# room_interface.net
KiCad netlist of a schematic drawn in EAGLE
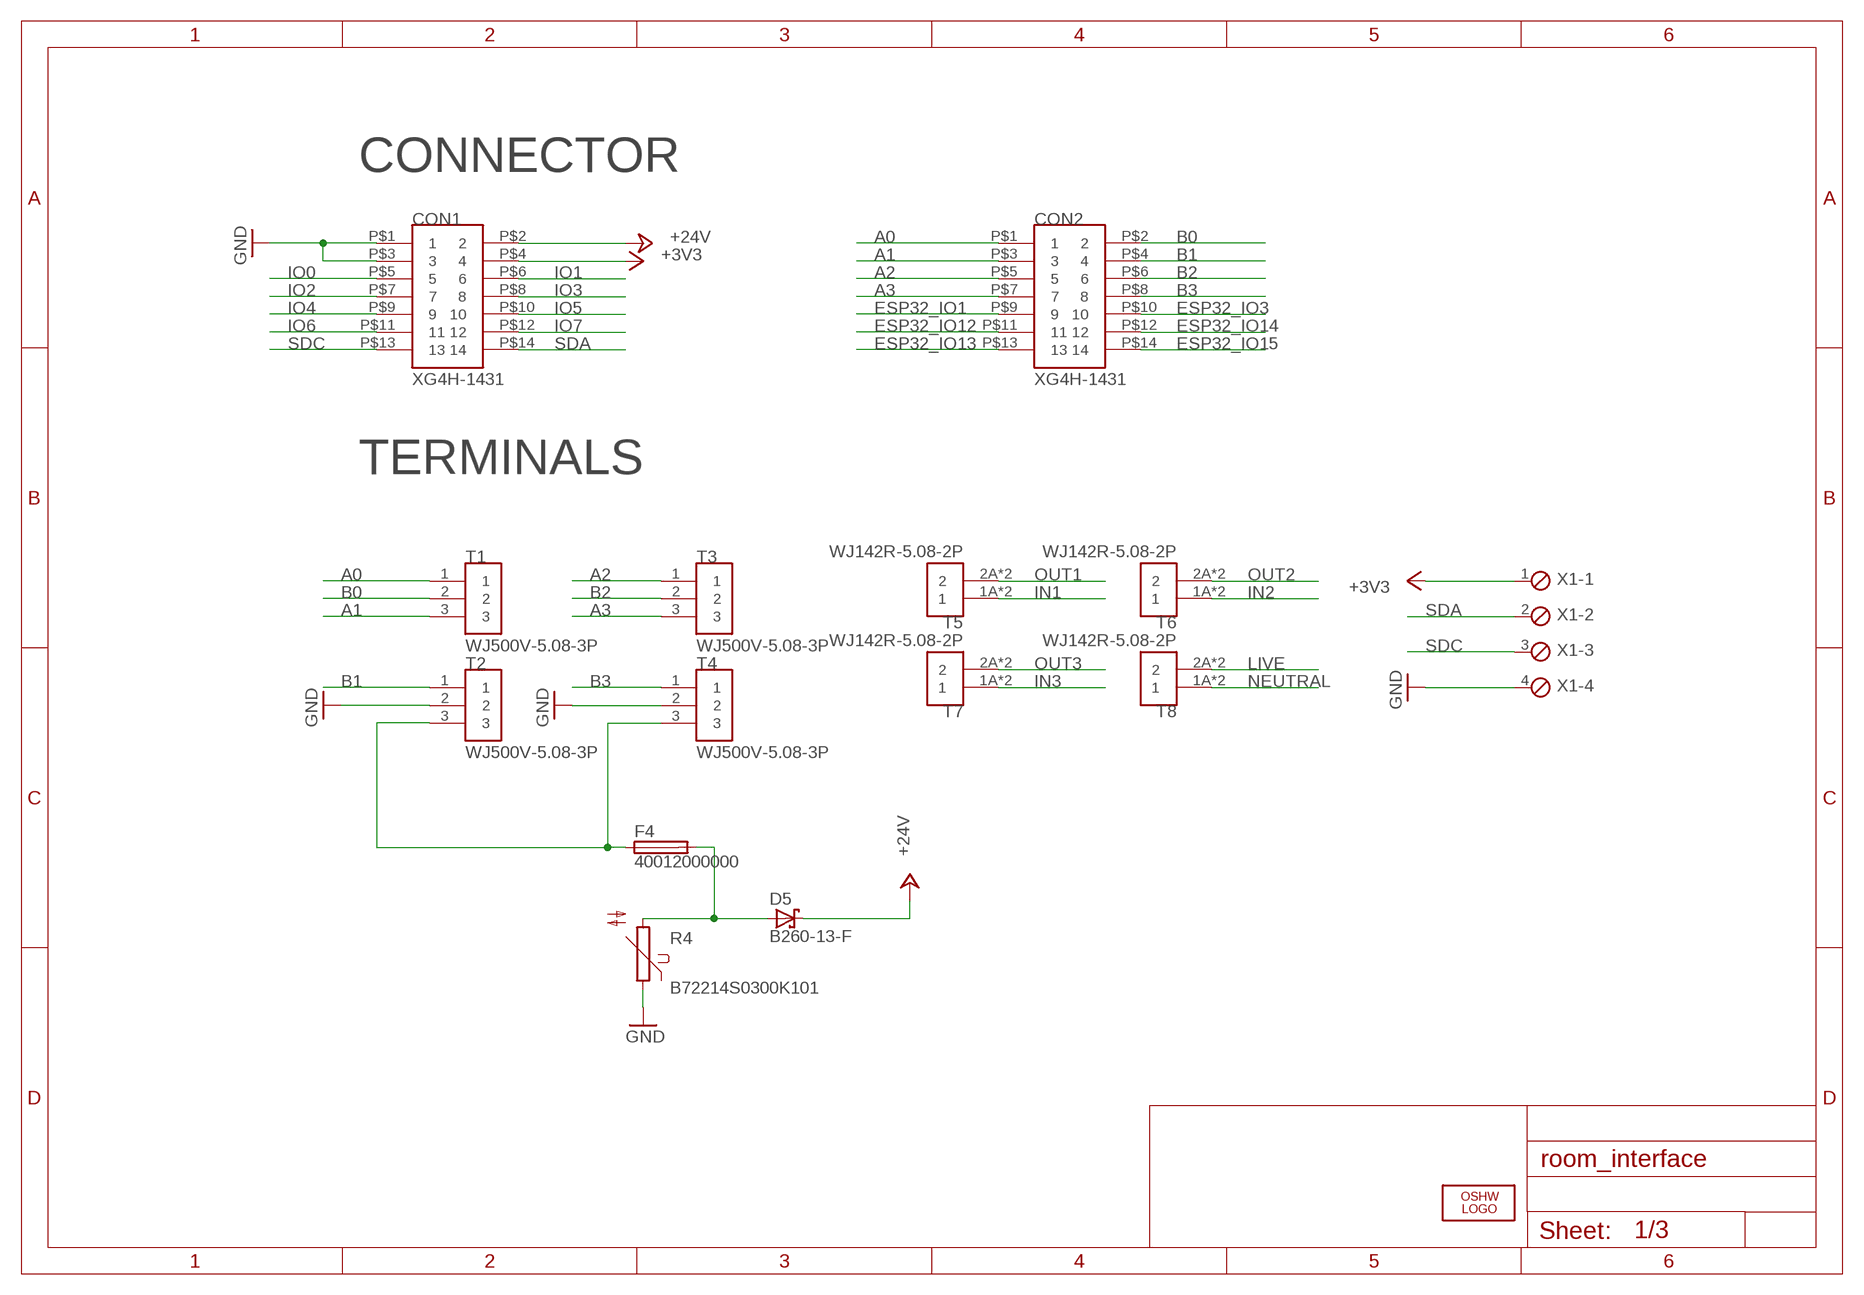
[diagram p0: schematic, sheet 1]
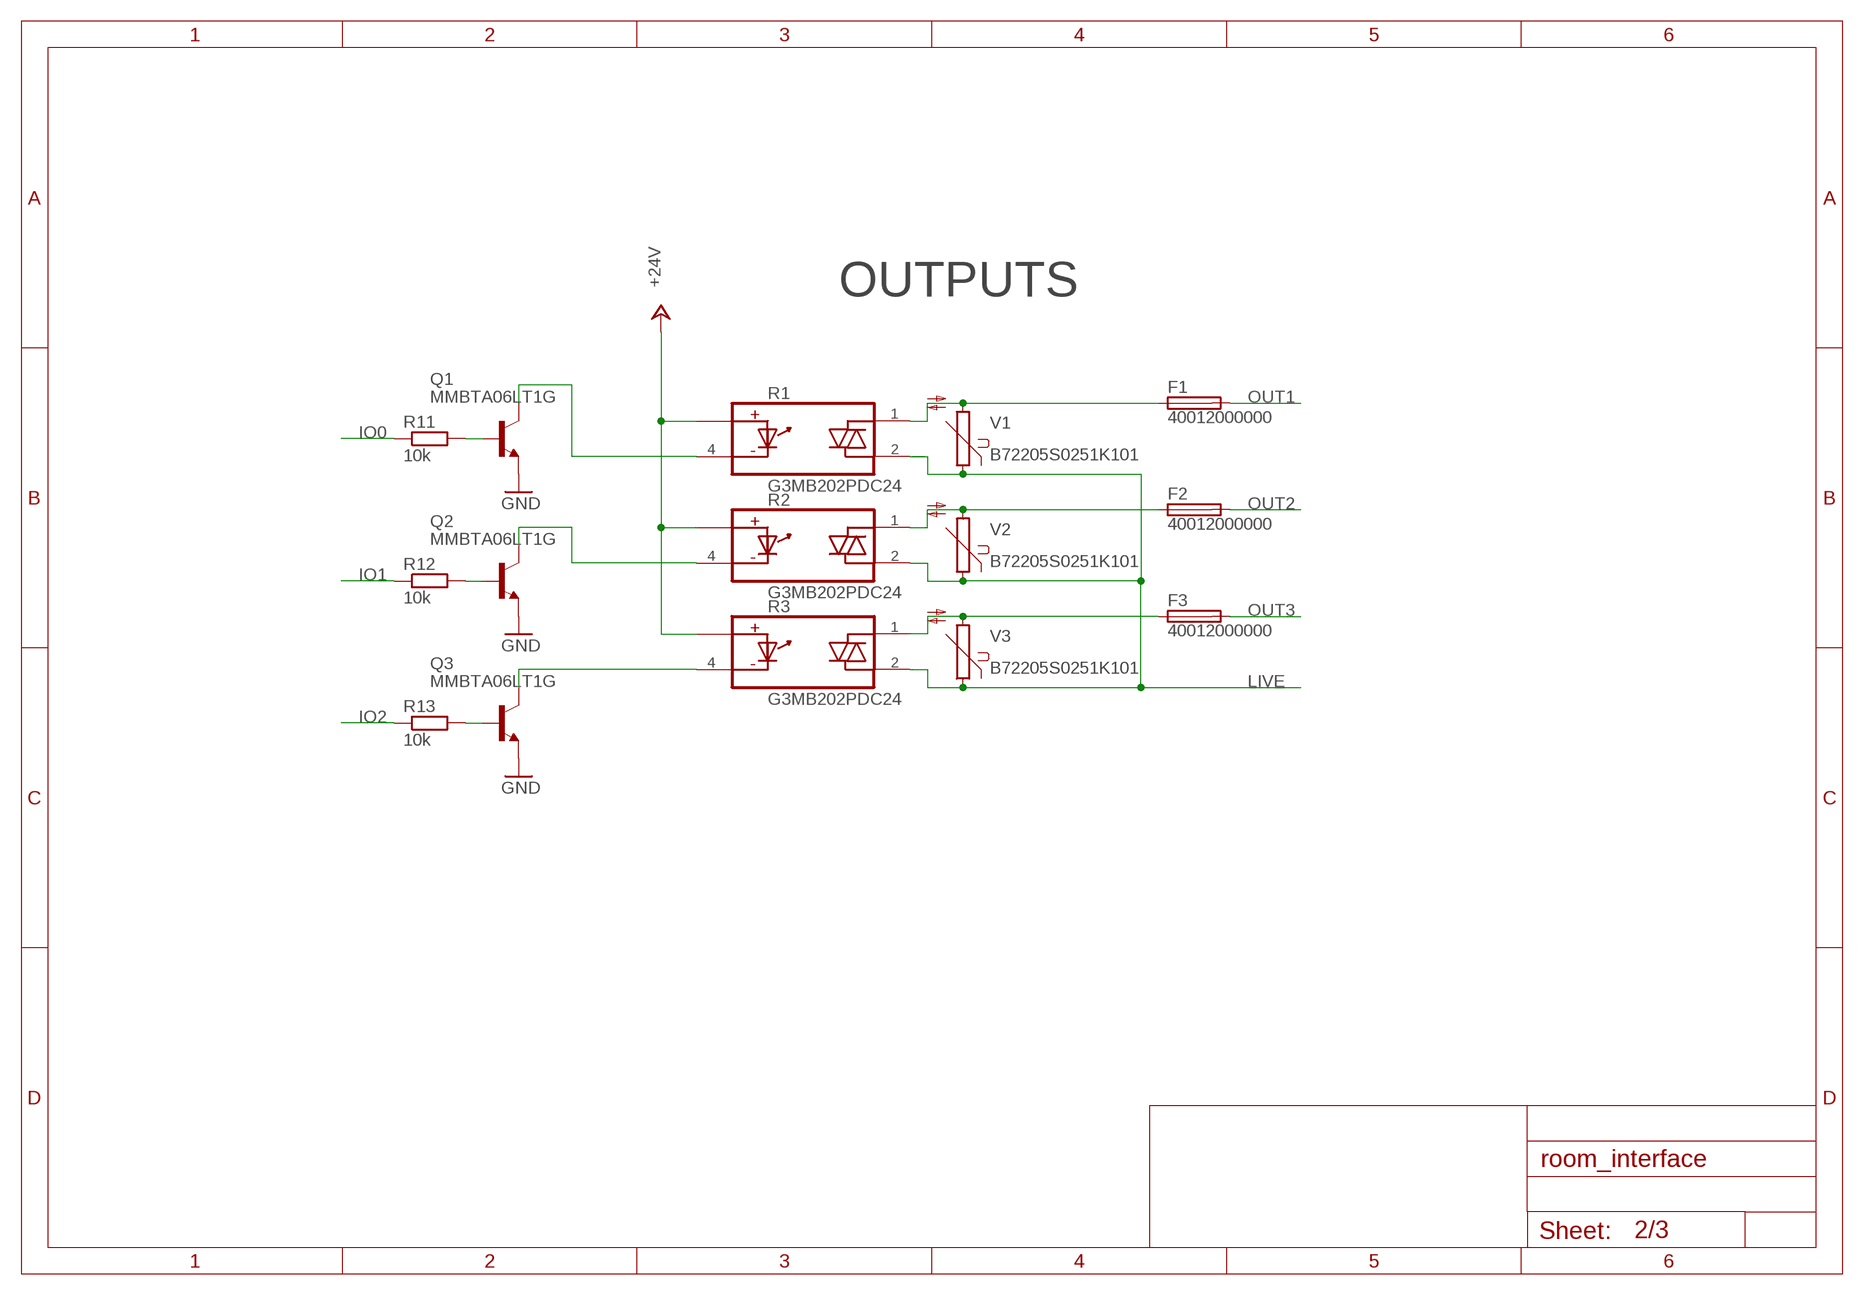
[diagram p1: schematic, sheet 2]
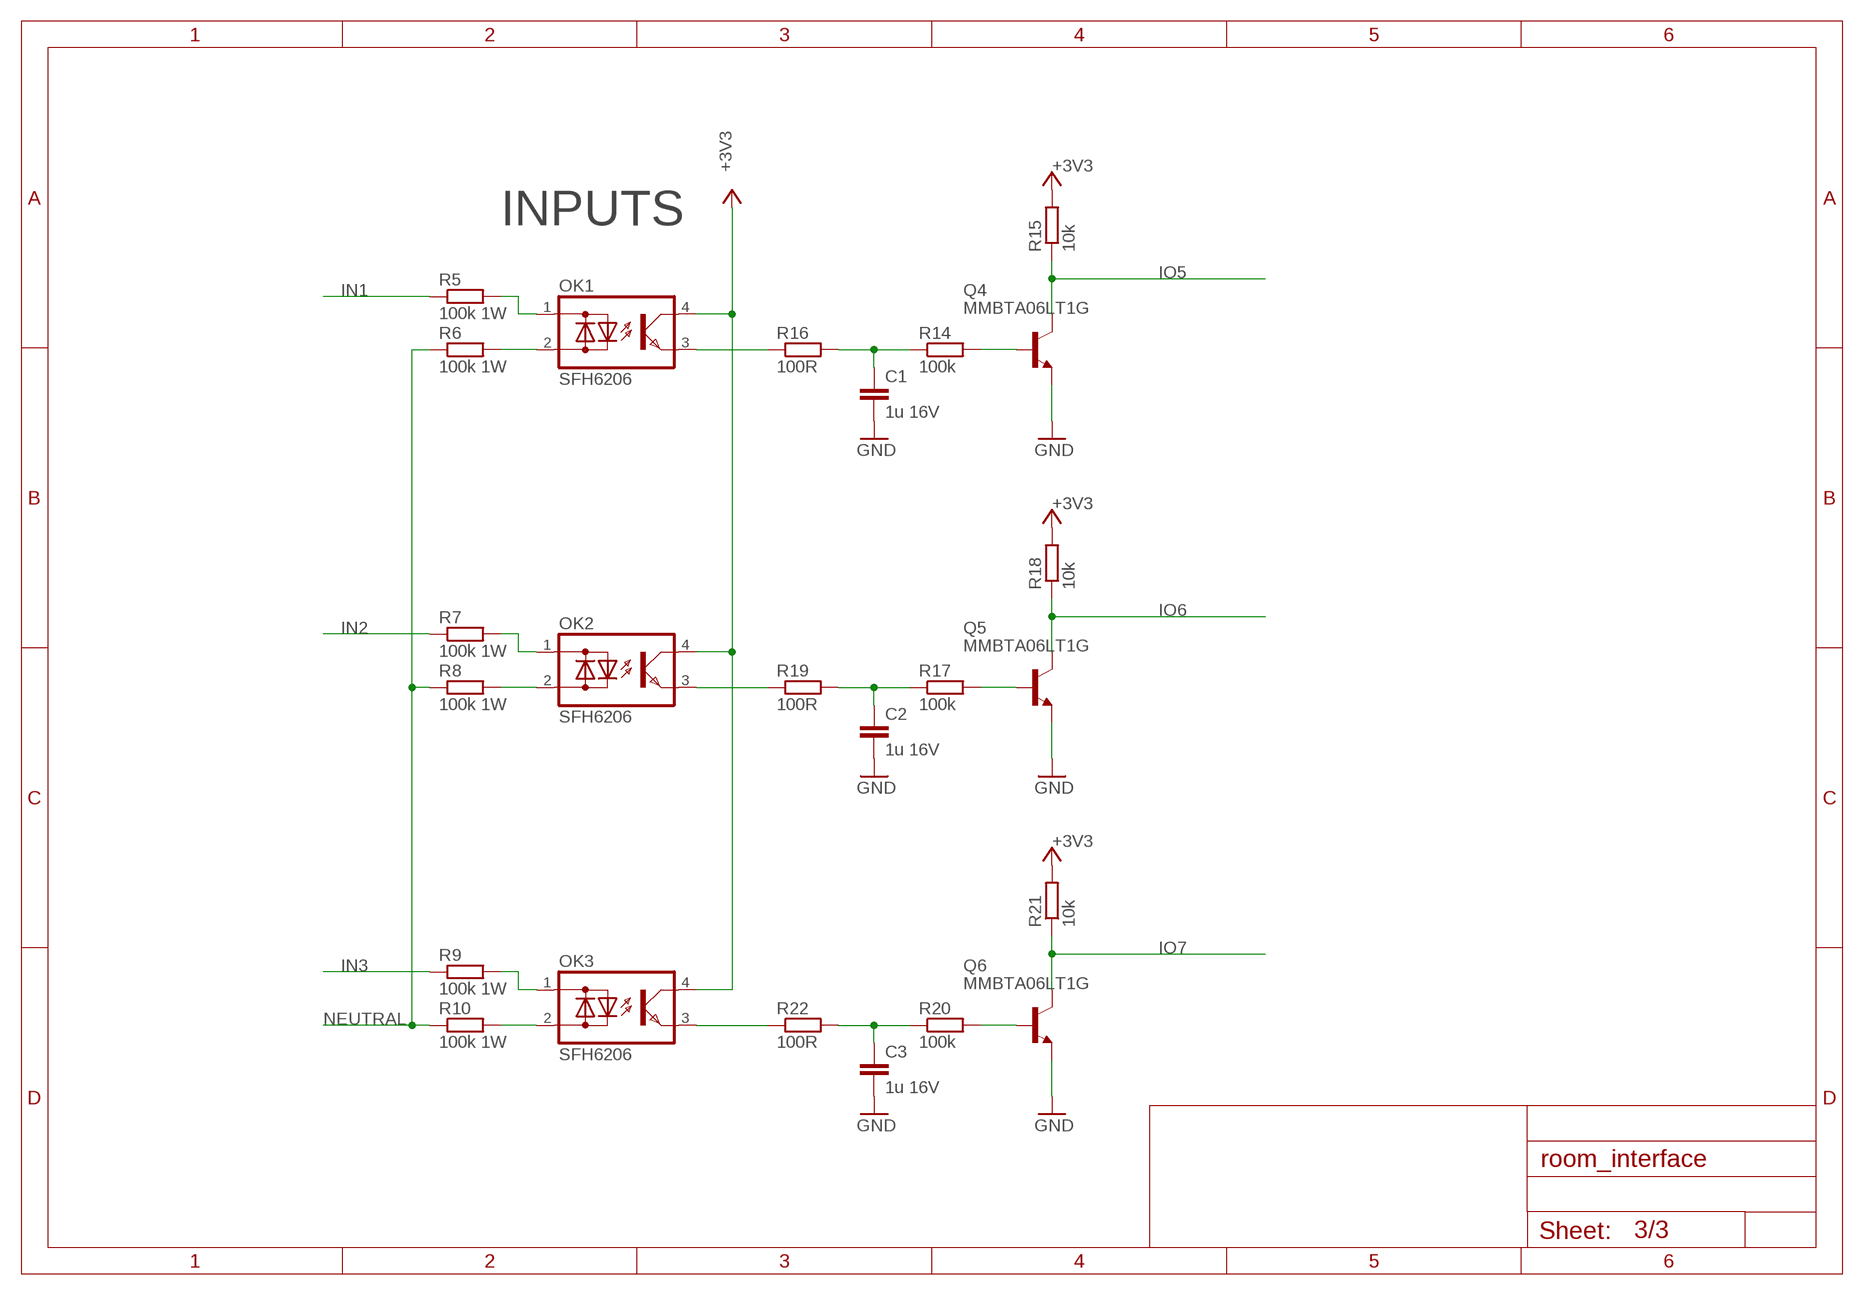
[diagram p2: schematic, sheet 3]

(export (version "E")
  (design (tool "Eeschema 10.0.6"))
  (components
    (comp (ref "C1")
      (value "1u 16V")
      (footprint "eagle-import:C0805")
      (libsource (lib "eagle-import") (part "C-EUC0805"))
    )
    (comp (ref "C2")
      (value "1u 16V")
      (footprint "eagle-import:C0805")
      (libsource (lib "eagle-import") (part "C-EUC0805"))
    )
    (comp (ref "C3")
      (value "1u 16V")
      (footprint "eagle-import:C0805")
      (libsource (lib "eagle-import") (part "C-EUC0805"))
    )
    (comp (ref "OK1")
      (value "SFH6206")
      (footprint "eagle-import:DIL4-SMD")
      (fields (field (name "MF") "VISHAY/TELEFUNKEN") (field (name "MPN") "SFH6206-3"))
      (libsource (lib "eagle-import") (part "SFH6206"))
    )
    (comp (ref "OK2")
      (value "SFH6206")
      (footprint "eagle-import:DIL4-SMD")
      (fields (field (name "MF") "VISHAY/TELEFUNKEN") (field (name "MPN") "SFH6206-3"))
      (libsource (lib "eagle-import") (part "SFH6206"))
    )
    (comp (ref "OK3")
      (value "SFH6206")
      (footprint "eagle-import:DIL4-SMD")
      (fields (field (name "MF") "VISHAY/TELEFUNKEN") (field (name "MPN") "SFH6206-3"))
      (libsource (lib "eagle-import") (part "SFH6206"))
    )
    (comp (ref "Q4")
      (value "MMBTA06LT1G")
      (footprint "eagle-import:SOT23-BEC")
      (libsource (lib "eagle-import") (part "BC849SMD"))
    )
    (comp (ref "Q5")
      (value "MMBTA06LT1G")
      (footprint "eagle-import:SOT23-BEC")
      (libsource (lib "eagle-import") (part "BC849SMD"))
    )
    (comp (ref "Q6")
      (value "MMBTA06LT1G")
      (footprint "eagle-import:SOT23-BEC")
      (libsource (lib "eagle-import") (part "BC849SMD"))
    )
    (comp (ref "R5")
      (value "100k 1W")
      (footprint "eagle-import:R2010")
      (libsource (lib "eagle-import") (part "R-EU_R2010"))
    )
    (comp (ref "R6")
      (value "100k 1W")
      (footprint "eagle-import:R2010")
      (libsource (lib "eagle-import") (part "R-EU_R2010"))
    )
    (comp (ref "R7")
      (value "100k 1W")
      (footprint "eagle-import:R2010")
      (libsource (lib "eagle-import") (part "R-EU_R2010"))
    )
    (comp (ref "R8")
      (value "100k 1W")
      (footprint "eagle-import:R2010")
      (libsource (lib "eagle-import") (part "R-EU_R2010"))
    )
    (comp (ref "R9")
      (value "100k 1W")
      (footprint "eagle-import:R2010")
      (libsource (lib "eagle-import") (part "R-EU_R2010"))
    )
    (comp (ref "R10")
      (value "100k 1W")
      (footprint "eagle-import:R2010")
      (libsource (lib "eagle-import") (part "R-EU_R2010"))
    )
    (comp (ref "R14")
      (value "100k")
      (footprint "eagle-import:R1206")
      (libsource (lib "eagle-import") (part "R-EU_R1206"))
    )
    (comp (ref "R15")
      (value "10k")
      (footprint "eagle-import:R1206")
      (libsource (lib "eagle-import") (part "R-EU_R1206"))
    )
    (comp (ref "R16")
      (value "100R")
      (footprint "eagle-import:R1206")
      (libsource (lib "eagle-import") (part "R-EU_R1206"))
    )
    (comp (ref "R17")
      (value "100k")
      (footprint "eagle-import:R1206")
      (libsource (lib "eagle-import") (part "R-EU_R1206"))
    )
    (comp (ref "R18")
      (value "10k")
      (footprint "eagle-import:R1206")
      (libsource (lib "eagle-import") (part "R-EU_R1206"))
    )
    (comp (ref "R19")
      (value "100R")
      (footprint "eagle-import:R1206")
      (libsource (lib "eagle-import") (part "R-EU_R1206"))
    )
    (comp (ref "R20")
      (value "100k")
      (footprint "eagle-import:R1206")
      (libsource (lib "eagle-import") (part "R-EU_R1206"))
    )
    (comp (ref "R21")
      (value "10k")
      (footprint "eagle-import:R1206")
      (libsource (lib "eagle-import") (part "R-EU_R1206"))
    )
    (comp (ref "R22")
      (value "100R")
      (footprint "eagle-import:R1206")
      (libsource (lib "eagle-import") (part "R-EU_R1206"))
    )
    (comp (ref "CON1")
      (value "XG4H-1431")
      (footprint "eagle-import:XG4H-1431")
      (libsource (lib "eagle-import") (part "XG4H-1431"))
    )
    (comp (ref "CON2")
      (value "XG4H-1431")
      (footprint "eagle-import:XG4H-1431")
      (libsource (lib "eagle-import") (part "XG4H-1431"))
    )
    (comp (ref "D5")
      (value "B260-13-F")
      (footprint "eagle-import:SMB")
      (libsource (lib "eagle-import") (part "MBRS130LT3"))
    )
    (comp (ref "F4")
      (value "40012000000")
      (footprint "eagle-import:400")
      (libsource (lib "eagle-import") (part "40012000000"))
    )
    (comp (ref "LOGO1")
      (value "OSHW_LOGO_FILLX0350-NT")
      (footprint "eagle-import:OSHW_FILLX350_NOTEXT")
      (libsource (lib "eagle-import") (part "OSHW_LOGO_FILLX0350-NT"))
    )
    (comp (ref "R4")
      (value "B72214S0300K101")
      (footprint "eagle-import:S14K300")
      (libsource (lib "eagle-import") (part "S14K300"))
    )
    (comp (ref "T1")
      (value "WJ500V-5.08-3P")
      (footprint "eagle-import:WJ500V-5.08-3P")
      (libsource (lib "eagle-import") (part "WJ500V-5.08-3P"))
    )
    (comp (ref "T2")
      (value "WJ500V-5.08-3P")
      (footprint "eagle-import:WJ500V-5.08-3P")
      (libsource (lib "eagle-import") (part "WJ500V-5.08-3P"))
    )
    (comp (ref "T3")
      (value "WJ500V-5.08-3P")
      (footprint "eagle-import:WJ500V-5.08-3P")
      (libsource (lib "eagle-import") (part "WJ500V-5.08-3P"))
    )
    (comp (ref "T4")
      (value "WJ500V-5.08-3P")
      (footprint "eagle-import:WJ500V-5.08-3P")
      (libsource (lib "eagle-import") (part "WJ500V-5.08-3P"))
    )
    (comp (ref "T5")
      (value "WJ142R-5.08-2P")
      (footprint "eagle-import:WJ142R.5.08-2P")
      (libsource (lib "eagle-import") (part "WJ142R-5.08-2P"))
    )
    (comp (ref "T6")
      (value "WJ142R-5.08-2P")
      (footprint "eagle-import:WJ142R.5.08-2P")
      (libsource (lib "eagle-import") (part "WJ142R-5.08-2P"))
    )
    (comp (ref "T7")
      (value "WJ142R-5.08-2P")
      (footprint "eagle-import:WJ142R.5.08-2P")
      (libsource (lib "eagle-import") (part "WJ142R-5.08-2P"))
    )
    (comp (ref "T8")
      (value "WJ142R-5.08-2P")
      (footprint "eagle-import:WJ142R.5.08-2P")
      (libsource (lib "eagle-import") (part "WJ142R-5.08-2P"))
    )
    (comp (ref "X1")
      (value "MPT4")
      (footprint "eagle-import:4POL254")
      (libsource (lib "eagle-import") (part "MPT4"))
    )
    (comp (ref "F1")
      (value "40012000000")
      (footprint "eagle-import:400")
      (libsource (lib "eagle-import") (part "40012000000"))
    )
    (comp (ref "F2")
      (value "40012000000")
      (footprint "eagle-import:400")
      (libsource (lib "eagle-import") (part "40012000000"))
    )
    (comp (ref "F3")
      (value "40012000000")
      (footprint "eagle-import:400")
      (libsource (lib "eagle-import") (part "40012000000"))
    )
    (comp (ref "Q1")
      (value "MMBTA06LT1G")
      (footprint "eagle-import:SOT23-BEC")
      (libsource (lib "eagle-import") (part "BC849SMD"))
    )
    (comp (ref "Q2")
      (value "MMBTA06LT1G")
      (footprint "eagle-import:SOT23-BEC")
      (libsource (lib "eagle-import") (part "BC849SMD"))
    )
    (comp (ref "Q3")
      (value "MMBTA06LT1G")
      (footprint "eagle-import:SOT23-BEC")
      (libsource (lib "eagle-import") (part "BC849SMD"))
    )
    (comp (ref "R1")
      (value "G3MB202PDC24")
      (footprint "eagle-import:RELAY_G3MB202PDC12")
      (libsource (lib "eagle-import") (part "RELAY_G3MB202PDC5"))
    )
    (comp (ref "R2")
      (value "G3MB202PDC24")
      (footprint "eagle-import:RELAY_G3MB202PDC12")
      (libsource (lib "eagle-import") (part "RELAY_G3MB202PDC5"))
    )
    (comp (ref "R3")
      (value "G3MB202PDC24")
      (footprint "eagle-import:RELAY_G3MB202PDC12")
      (libsource (lib "eagle-import") (part "RELAY_G3MB202PDC5"))
    )
    (comp (ref "R11")
      (value "10k")
      (footprint "eagle-import:R1206")
      (libsource (lib "eagle-import") (part "R-EU_R1206"))
    )
    (comp (ref "R12")
      (value "10k")
      (footprint "eagle-import:R1206")
      (libsource (lib "eagle-import") (part "R-EU_R1206"))
    )
    (comp (ref "R13")
      (value "10k")
      (footprint "eagle-import:R1206")
      (libsource (lib "eagle-import") (part "R-EU_R1206"))
    )
    (comp (ref "V1")
      (value "B72205S0251K101")
      (footprint "eagle-import:S05K250")
      (libsource (lib "eagle-import") (part "S05K250"))
    )
    (comp (ref "V2")
      (value "B72205S0251K101")
      (footprint "eagle-import:S05K250")
      (libsource (lib "eagle-import") (part "S05K250"))
    )
    (comp (ref "V3")
      (value "B72205S0251K101")
      (footprint "eagle-import:S05K250")
      (libsource (lib "eagle-import") (part "S05K250"))
    )
  )
  (nets
    (net (code "1") (name "+3V3") (class "Default")
      (node (ref "CON1") (pin "P$4") (pinfunction "4_P$4") (pintype "passive"))
      (node (ref "OK1") (pin "4") (pinfunction "C_4") (pintype "passive"))
      (node (ref "OK2") (pin "4") (pinfunction "C_4") (pintype "passive"))
      (node (ref "OK3") (pin "4") (pinfunction "C_4") (pintype "passive"))
      (node (ref "R15") (pin "2") (pinfunction "2_2") (pintype "passive"))
      (node (ref "R18") (pin "2") (pinfunction "2_2") (pintype "passive"))
      (node (ref "R21") (pin "2") (pinfunction "2_2") (pintype "passive"))
      (node (ref "X1") (pin "1") (pinfunction "1_1") (pintype "passive"))
    )
    (net (code "2") (name "+24V") (class "Default")
      (node (ref "CON1") (pin "P$2") (pinfunction "2_P$2") (pintype "passive"))
      (node (ref "D5") (pin "C") (pinfunction "C_C") (pintype "passive"))
      (node (ref "R1") (pin "3") (pinfunction "IN+_3") (pintype "input"))
      (node (ref "R2") (pin "3") (pinfunction "IN+_3") (pintype "input"))
      (node (ref "R3") (pin "3") (pinfunction "IN+_3") (pintype "input"))
    )
    (net (code "3") (name "A0") (class "Default")
      (node (ref "CON2") (pin "P$1") (pinfunction "1_P$1") (pintype "passive"))
      (node (ref "T1") (pin "1") (pinfunction "1_1") (pintype "passive"))
    )
    (net (code "4") (name "A1") (class "Default")
      (node (ref "CON2") (pin "P$3") (pinfunction "3_P$3") (pintype "passive"))
      (node (ref "T1") (pin "3") (pinfunction "3_3") (pintype "passive"))
    )
    (net (code "5") (name "A2") (class "Default")
      (node (ref "CON2") (pin "P$5") (pinfunction "5_P$5") (pintype "passive"))
      (node (ref "T3") (pin "1") (pinfunction "1_1") (pintype "passive"))
    )
    (net (code "6") (name "A3") (class "Default")
      (node (ref "CON2") (pin "P$7") (pinfunction "7_P$7") (pintype "passive"))
      (node (ref "T3") (pin "3") (pinfunction "3_3") (pintype "passive"))
    )
    (net (code "7") (name "B0") (class "Default")
      (node (ref "CON2") (pin "P$2") (pinfunction "2_P$2") (pintype "passive"))
      (node (ref "T1") (pin "2") (pinfunction "2_2") (pintype "passive"))
    )
    (net (code "8") (name "B1") (class "Default")
      (node (ref "CON2") (pin "P$4") (pinfunction "4_P$4") (pintype "passive"))
      (node (ref "T2") (pin "1") (pinfunction "1_1") (pintype "passive"))
    )
    (net (code "9") (name "B2") (class "Default")
      (node (ref "CON2") (pin "P$6") (pinfunction "6_P$6") (pintype "passive"))
      (node (ref "T3") (pin "2") (pinfunction "2_2") (pintype "passive"))
    )
    (net (code "10") (name "B3") (class "Default")
      (node (ref "CON2") (pin "P$8") (pinfunction "8_P$8") (pintype "passive"))
      (node (ref "T4") (pin "1") (pinfunction "1_1") (pintype "passive"))
    )
    (net (code "11") (name "ESP32_IO1") (class "Default")
      (node (ref "CON2") (pin "P$9") (pinfunction "9_P$9") (pintype "passive"))
    )
    (net (code "12") (name "ESP32_IO3") (class "Default")
      (node (ref "CON2") (pin "P$10") (pinfunction "10_P$10") (pintype "passive"))
    )
    (net (code "13") (name "ESP32_IO12") (class "Default")
      (node (ref "CON2") (pin "P$11") (pinfunction "11_P$11") (pintype "passive"))
    )
    (net (code "14") (name "ESP32_IO13") (class "Default")
      (node (ref "CON2") (pin "P$13") (pinfunction "13_P$13") (pintype "passive"))
    )
    (net (code "15") (name "ESP32_IO14") (class "Default")
      (node (ref "CON2") (pin "P$12") (pinfunction "12_P$12") (pintype "passive"))
    )
    (net (code "16") (name "ESP32_IO15") (class "Default")
      (node (ref "CON2") (pin "P$14") (pinfunction "14_P$14") (pintype "passive"))
    )
    (net (code "17") (name "GND") (class "Default")
      (node (ref "C1") (pin "2") (pinfunction "2_2") (pintype "passive"))
      (node (ref "C2") (pin "2") (pinfunction "2_2") (pintype "passive"))
      (node (ref "C3") (pin "2") (pinfunction "2_2") (pintype "passive"))
      (node (ref "CON1") (pin "P$1") (pinfunction "1_P$1") (pintype "passive"))
      (node (ref "CON1") (pin "P$3") (pinfunction "3_P$3") (pintype "passive"))
      (node (ref "Q1") (pin "E") (pinfunction "E_E") (pintype "passive"))
      (node (ref "Q2") (pin "E") (pinfunction "E_E") (pintype "passive"))
      (node (ref "Q3") (pin "E") (pinfunction "E_E") (pintype "passive"))
      (node (ref "Q4") (pin "E") (pinfunction "E_E") (pintype "passive"))
      (node (ref "Q5") (pin "E") (pinfunction "E_E") (pintype "passive"))
      (node (ref "Q6") (pin "E") (pinfunction "E_E") (pintype "passive"))
      (node (ref "R4") (pin "1") (pinfunction "1_1") (pintype "passive"))
      (node (ref "T2") (pin "2") (pinfunction "2_2") (pintype "passive"))
      (node (ref "T4") (pin "2") (pinfunction "2_2") (pintype "passive"))
      (node (ref "X1") (pin "4") (pinfunction "1_4") (pintype "passive"))
    )
    (net (code "18") (name "IN1") (class "Default")
      (node (ref "R5") (pin "1") (pinfunction "1_1") (pintype "passive"))
      (node (ref "T5") (pin "1A") (pinfunction "1_1A") (pintype "passive"))
      (node (ref "T5") (pin "1B") (pinfunction "1_1B") (pintype "passive"))
    )
    (net (code "19") (name "IN2") (class "Default")
      (node (ref "R7") (pin "1") (pinfunction "1_1") (pintype "passive"))
      (node (ref "T6") (pin "1A") (pinfunction "1_1A") (pintype "passive"))
      (node (ref "T6") (pin "1B") (pinfunction "1_1B") (pintype "passive"))
    )
    (net (code "20") (name "IN3") (class "Default")
      (node (ref "R9") (pin "1") (pinfunction "1_1") (pintype "passive"))
      (node (ref "T7") (pin "1A") (pinfunction "1_1A") (pintype "passive"))
      (node (ref "T7") (pin "1B") (pinfunction "1_1B") (pintype "passive"))
    )
    (net (code "21") (name "IO0") (class "Default")
      (node (ref "CON1") (pin "P$5") (pinfunction "5_P$5") (pintype "passive"))
      (node (ref "R11") (pin "1") (pinfunction "1_1") (pintype "passive"))
    )
    (net (code "22") (name "IO1") (class "Default")
      (node (ref "CON1") (pin "P$6") (pinfunction "6_P$6") (pintype "passive"))
      (node (ref "R12") (pin "1") (pinfunction "1_1") (pintype "passive"))
    )
    (net (code "23") (name "IO2") (class "Default")
      (node (ref "CON1") (pin "P$7") (pinfunction "7_P$7") (pintype "passive"))
      (node (ref "R13") (pin "1") (pinfunction "1_1") (pintype "passive"))
    )
    (net (code "24") (name "IO3") (class "Default")
      (node (ref "CON1") (pin "P$8") (pinfunction "8_P$8") (pintype "passive"))
    )
    (net (code "25") (name "IO4") (class "Default")
      (node (ref "CON1") (pin "P$9") (pinfunction "9_P$9") (pintype "passive"))
    )
    (net (code "26") (name "IO5") (class "Default")
      (node (ref "CON1") (pin "P$10") (pinfunction "10_P$10") (pintype "passive"))
      (node (ref "Q4") (pin "C") (pinfunction "C_C") (pintype "passive"))
      (node (ref "R15") (pin "1") (pinfunction "1_1") (pintype "passive"))
    )
    (net (code "27") (name "IO6") (class "Default")
      (node (ref "CON1") (pin "P$11") (pinfunction "11_P$11") (pintype "passive"))
      (node (ref "Q5") (pin "C") (pinfunction "C_C") (pintype "passive"))
      (node (ref "R18") (pin "1") (pinfunction "1_1") (pintype "passive"))
    )
    (net (code "28") (name "IO7") (class "Default")
      (node (ref "CON1") (pin "P$12") (pinfunction "12_P$12") (pintype "passive"))
      (node (ref "Q6") (pin "C") (pinfunction "C_C") (pintype "passive"))
      (node (ref "R21") (pin "1") (pinfunction "1_1") (pintype "passive"))
    )
    (net (code "29") (name "LIVE") (class "Default")
      (node (ref "R1") (pin "2") (pinfunction "OUT2_2") (pintype "output"))
      (node (ref "R2") (pin "2") (pinfunction "OUT2_2") (pintype "output"))
      (node (ref "R3") (pin "2") (pinfunction "OUT2_2") (pintype "output"))
      (node (ref "T8") (pin "2A") (pinfunction "2_2A") (pintype "passive"))
      (node (ref "T8") (pin "2B") (pinfunction "2_2B") (pintype "passive"))
      (node (ref "V1") (pin "1") (pinfunction "1_1") (pintype "passive"))
      (node (ref "V2") (pin "1") (pinfunction "1_1") (pintype "passive"))
      (node (ref "V3") (pin "1") (pinfunction "1_1") (pintype "passive"))
    )
    (net (code "30") (name "NEUTRAL") (class "Default")
      (node (ref "R10") (pin "1") (pinfunction "1_1") (pintype "passive"))
      (node (ref "R6") (pin "1") (pinfunction "1_1") (pintype "passive"))
      (node (ref "R8") (pin "1") (pinfunction "1_1") (pintype "passive"))
      (node (ref "T8") (pin "1A") (pinfunction "1_1A") (pintype "passive"))
      (node (ref "T8") (pin "1B") (pinfunction "1_1B") (pintype "passive"))
    )
    (net (code "31") (name "Net-(C1-Pad1)") (class "Default")
      (node (ref "C1") (pin "1") (pinfunction "1_1") (pintype "passive"))
      (node (ref "R14") (pin "1") (pinfunction "1_1") (pintype "passive"))
      (node (ref "R16") (pin "2") (pinfunction "2_2") (pintype "passive"))
    )
    (net (code "32") (name "Net-(C2-Pad1)") (class "Default")
      (node (ref "C2") (pin "1") (pinfunction "1_1") (pintype "passive"))
      (node (ref "R17") (pin "1") (pinfunction "1_1") (pintype "passive"))
      (node (ref "R19") (pin "2") (pinfunction "2_2") (pintype "passive"))
    )
    (net (code "33") (name "Net-(C3-Pad1)") (class "Default")
      (node (ref "C3") (pin "1") (pinfunction "1_1") (pintype "passive"))
      (node (ref "R20") (pin "1") (pinfunction "1_1") (pintype "passive"))
      (node (ref "R22") (pin "2") (pinfunction "2_2") (pintype "passive"))
    )
    (net (code "34") (name "Net-(F1-1)") (class "Default")
      (node (ref "F1") (pin "P$1") (pinfunction "1_P$1") (pintype "passive"))
      (node (ref "R1") (pin "1") (pinfunction "OUT1_1") (pintype "output"))
      (node (ref "V1") (pin "2") (pinfunction "2_2") (pintype "passive"))
    )
    (net (code "35") (name "Net-(F2-1)") (class "Default")
      (node (ref "F2") (pin "P$1") (pinfunction "1_P$1") (pintype "passive"))
      (node (ref "R2") (pin "1") (pinfunction "OUT1_1") (pintype "output"))
      (node (ref "V2") (pin "2") (pinfunction "2_2") (pintype "passive"))
    )
    (net (code "36") (name "Net-(F3-1)") (class "Default")
      (node (ref "F3") (pin "P$1") (pinfunction "1_P$1") (pintype "passive"))
      (node (ref "R3") (pin "1") (pinfunction "OUT1_1") (pintype "output"))
      (node (ref "V3") (pin "2") (pinfunction "2_2") (pintype "passive"))
    )
    (net (code "37") (name "Net-(F4-1)") (class "Default")
      (node (ref "F4") (pin "P$1") (pinfunction "1_P$1") (pintype "passive"))
      (node (ref "T2") (pin "3") (pinfunction "3_3") (pintype "passive"))
      (node (ref "T4") (pin "3") (pinfunction "3_3") (pintype "passive"))
    )
    (net (code "38") (name "Net-(F4-2)") (class "Default")
      (node (ref "D5") (pin "A") (pinfunction "A_A") (pintype "passive"))
      (node (ref "F4") (pin "P$2") (pinfunction "2_P$2") (pintype "passive"))
      (node (ref "R4") (pin "2") (pinfunction "2_2") (pintype "passive"))
    )
    (net (code "39") (name "Net-(OK1-AC1)") (class "Default")
      (node (ref "OK1") (pin "1") (pinfunction "AC1_1") (pintype "passive"))
      (node (ref "R5") (pin "2") (pinfunction "2_2") (pintype "passive"))
    )
    (net (code "40") (name "Net-(OK1-AC2)") (class "Default")
      (node (ref "OK1") (pin "2") (pinfunction "AC2_2") (pintype "passive"))
      (node (ref "R6") (pin "2") (pinfunction "2_2") (pintype "passive"))
    )
    (net (code "41") (name "Net-(OK1-E)") (class "Default")
      (node (ref "OK1") (pin "3") (pinfunction "E_3") (pintype "passive"))
      (node (ref "R16") (pin "1") (pinfunction "1_1") (pintype "passive"))
    )
    (net (code "42") (name "Net-(OK2-AC1)") (class "Default")
      (node (ref "OK2") (pin "1") (pinfunction "AC1_1") (pintype "passive"))
      (node (ref "R7") (pin "2") (pinfunction "2_2") (pintype "passive"))
    )
    (net (code "43") (name "Net-(OK2-AC2)") (class "Default")
      (node (ref "OK2") (pin "2") (pinfunction "AC2_2") (pintype "passive"))
      (node (ref "R8") (pin "2") (pinfunction "2_2") (pintype "passive"))
    )
    (net (code "44") (name "Net-(OK2-E)") (class "Default")
      (node (ref "OK2") (pin "3") (pinfunction "E_3") (pintype "passive"))
      (node (ref "R19") (pin "1") (pinfunction "1_1") (pintype "passive"))
    )
    (net (code "45") (name "Net-(OK3-AC1)") (class "Default")
      (node (ref "OK3") (pin "1") (pinfunction "AC1_1") (pintype "passive"))
      (node (ref "R9") (pin "2") (pinfunction "2_2") (pintype "passive"))
    )
    (net (code "46") (name "Net-(OK3-AC2)") (class "Default")
      (node (ref "OK3") (pin "2") (pinfunction "AC2_2") (pintype "passive"))
      (node (ref "R10") (pin "2") (pinfunction "2_2") (pintype "passive"))
    )
    (net (code "47") (name "Net-(OK3-E)") (class "Default")
      (node (ref "OK3") (pin "3") (pinfunction "E_3") (pintype "passive"))
      (node (ref "R22") (pin "1") (pinfunction "1_1") (pintype "passive"))
    )
    (net (code "48") (name "Net-(Q1-PadB)") (class "Default")
      (node (ref "Q1") (pin "B") (pinfunction "B_B") (pintype "passive"))
      (node (ref "R11") (pin "2") (pinfunction "2_2") (pintype "passive"))
    )
    (net (code "49") (name "Net-(Q2-PadB)") (class "Default")
      (node (ref "Q2") (pin "B") (pinfunction "B_B") (pintype "passive"))
      (node (ref "R12") (pin "2") (pinfunction "2_2") (pintype "passive"))
    )
    (net (code "50") (name "Net-(Q3-PadB)") (class "Default")
      (node (ref "Q3") (pin "B") (pinfunction "B_B") (pintype "passive"))
      (node (ref "R13") (pin "2") (pinfunction "2_2") (pintype "passive"))
    )
    (net (code "51") (name "Net-(Q4-PadB)") (class "Default")
      (node (ref "Q4") (pin "B") (pinfunction "B_B") (pintype "passive"))
      (node (ref "R14") (pin "2") (pinfunction "2_2") (pintype "passive"))
    )
    (net (code "52") (name "Net-(Q5-PadB)") (class "Default")
      (node (ref "Q5") (pin "B") (pinfunction "B_B") (pintype "passive"))
      (node (ref "R17") (pin "2") (pinfunction "2_2") (pintype "passive"))
    )
    (net (code "53") (name "Net-(Q6-PadB)") (class "Default")
      (node (ref "Q6") (pin "B") (pinfunction "B_B") (pintype "passive"))
      (node (ref "R20") (pin "2") (pinfunction "2_2") (pintype "passive"))
    )
    (net (code "54") (name "Net-(R1-IN-)") (class "Default")
      (node (ref "Q1") (pin "C") (pinfunction "C_C") (pintype "passive"))
      (node (ref "R1") (pin "4") (pinfunction "IN-_4") (pintype "input"))
    )
    (net (code "55") (name "Net-(R2-IN-)") (class "Default")
      (node (ref "Q2") (pin "C") (pinfunction "C_C") (pintype "passive"))
      (node (ref "R2") (pin "4") (pinfunction "IN-_4") (pintype "input"))
    )
    (net (code "56") (name "Net-(R3-IN-)") (class "Default")
      (node (ref "Q3") (pin "C") (pinfunction "C_C") (pintype "passive"))
      (node (ref "R3") (pin "4") (pinfunction "IN-_4") (pintype "input"))
    )
    (net (code "57") (name "OUT1") (class "Default")
      (node (ref "F1") (pin "P$2") (pinfunction "2_P$2") (pintype "passive"))
      (node (ref "T5") (pin "2A") (pinfunction "2_2A") (pintype "passive"))
      (node (ref "T5") (pin "2B") (pinfunction "2_2B") (pintype "passive"))
    )
    (net (code "58") (name "OUT2") (class "Default")
      (node (ref "F2") (pin "P$2") (pinfunction "2_P$2") (pintype "passive"))
      (node (ref "T6") (pin "2A") (pinfunction "2_2A") (pintype "passive"))
      (node (ref "T6") (pin "2B") (pinfunction "2_2B") (pintype "passive"))
    )
    (net (code "59") (name "OUT3") (class "Default")
      (node (ref "F3") (pin "P$2") (pinfunction "2_P$2") (pintype "passive"))
      (node (ref "T7") (pin "2A") (pinfunction "2_2A") (pintype "passive"))
      (node (ref "T7") (pin "2B") (pinfunction "2_2B") (pintype "passive"))
    )
    (net (code "60") (name "SDA") (class "Default")
      (node (ref "CON1") (pin "P$14") (pinfunction "14_P$14") (pintype "passive"))
      (node (ref "X1") (pin "2") (pinfunction "1_2") (pintype "passive"))
    )
    (net (code "61") (name "SDC") (class "Default")
      (node (ref "CON1") (pin "P$13") (pinfunction "13_P$13") (pintype "passive"))
      (node (ref "X1") (pin "3") (pinfunction "1_3") (pintype "passive"))
    )
  )
)
